# VccConnSch.net
KiCad netlist of a schematic drawn in Altium Designer
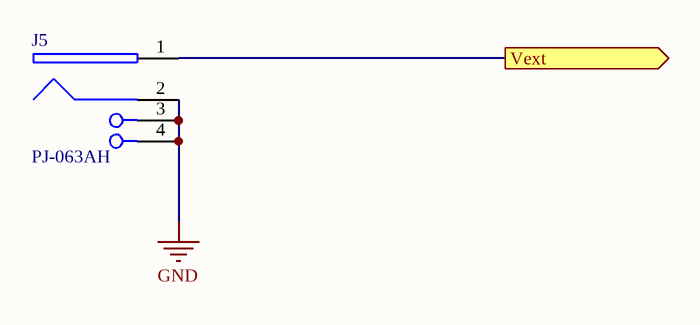
[diagram p0: VccConnSch.SchDoc]

(export (version "E")
  (design (tool "Eeschema 10.0.6"))
  (components
    (comp (ref "J5")
      (value "PJ-063AH")
      (footprint "CUI-PJ-063AH_V")
      (fields (field (name "MANUFACTURER") "CUIInc."))
      (libsource (lib "Altium Content Vault") (part "JACK-2CD2_A"))
    )
  )
  (nets
    (net (code "1") (name "/Vext") (class "Default")
      (node (ref "J5") (pin "1") (pinfunction "1_1") (pintype "passive"))
    )
    (net (code "2") (name "GND") (class "Default")
      (node (ref "J5") (pin "2") (pinfunction "2_2") (pintype "passive"))
      (node (ref "J5") (pin "3") (pinfunction "SHLD_3") (pintype "passive"))
      (node (ref "J5") (pin "4") (pinfunction "SHLD_4") (pintype "passive"))
    )
  )
)
